# 15_Debug_schdoc.net
KiCad netlist of a schematic drawn in Altium Designer
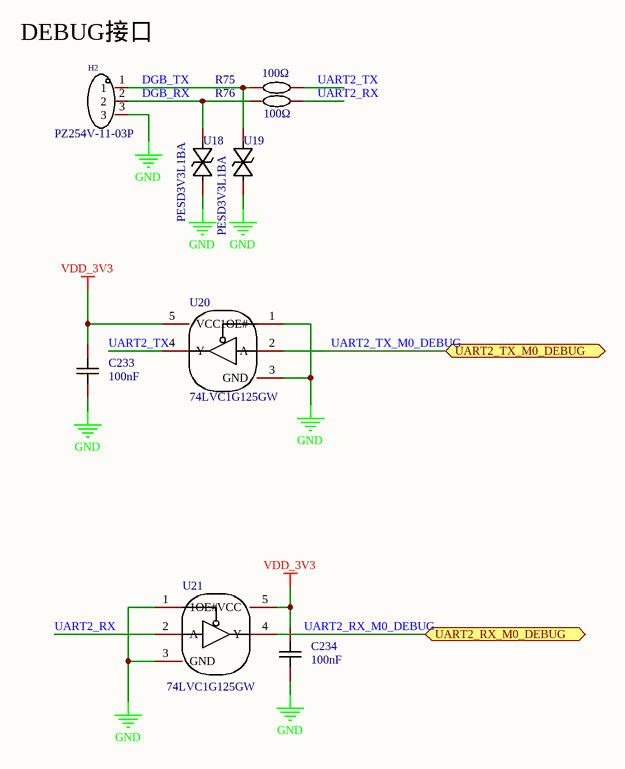
[diagram p0: 15_Debug接口.schdoc.schdoc]

(export (version "E")
  (design (tool "Eeschema 10.0.6"))
  (components
    (comp (ref "C233")
      (value "100nF")
      (footprint "C0603")
      (fields
        (field (name "NAME") "100nF")
        (field (name "MANUFACTURER") "YAGEO(国巨)")
        (field (name "MANUFACTURER PART") "CC0603KRX7R9BB104")
        (field (name "TOLERANCE") "±10%")
      )
      (libsource (lib "altium-import") (part "root_1_CC0603KRX7R9BB104_"))
    )
    (comp (ref "C234")
      (value "100nF")
      (footprint "C0603")
      (fields
        (field (name "NAME") "100nF")
        (field (name "MANUFACTURER") "YAGEO(国巨)")
        (field (name "MANUFACTURER PART") "CC0603KRX7R9BB104")
        (field (name "TOLERANCE") "±10%")
      )
      (libsource (lib "altium-import") (part "root_1_CC0603KRX7R9BB104_"))
    )
    (comp (ref "H2")
      (value "PZ254V-11-03P")
      (footprint "HDR-TH_3P-P2.54-V-M")
      (fields (field (name "NAME") "PZ254V-11-03P") (field (name "MANUFACTURER") "XFCN(兴飞)"))
      (libsource (lib "altium-import") (part "root_0_mirrored_PZ254V-11-03P_"))
    )
    (comp (ref "R75")
      (value "100Ω")
      (footprint "R0603")
      (fields
        (field (name "NAME") "100Ω")
        (field (name "MANUFACTURER") "UNI-ROYAL(厚声)")
        (field (name "MANUFACTURER PART") "0603WAF1000T5E")
        (field (name "TOLERANCE") "±1%")
      )
      (libsource (lib "altium-import") (part "root_0_0603WAF1000T5E_"))
    )
    (comp (ref "R76")
      (value "100Ω")
      (footprint "R0603")
      (fields
        (field (name "NAME") "100Ω")
        (field (name "MANUFACTURER") "UNI-ROYAL(厚声)")
        (field (name "MANUFACTURER PART") "0603WAF1000T5E")
        (field (name "TOLERANCE") "±1%")
      )
      (libsource (lib "altium-import") (part "root_0_0603WAF1000T5E_"))
    )
    (comp (ref "U18")
      (value "PESD3V3L1BA")
      (footprint "SOD-323_L1.7-W1.3-LS2.6-BI")
      (fields (field (name "NAME") "PESD3V3L1BA") (field (name "MANUFACTURER") "UMW(友台半导体)"))
      (libsource (lib "altium-import") (part "root_1_PESD3V3L1BA_C2687129_"))
    )
    (comp (ref "U19")
      (value "PESD3V3L1BA")
      (footprint "SOD-323_L1.7-W1.3-LS2.6-BI")
      (fields (field (name "NAME") "PESD3V3L1BA") (field (name "MANUFACTURER") "UMW(友台半导体)"))
      (libsource (lib "altium-import") (part "root_1_PESD3V3L1BA_C2687129_"))
    )
    (comp (ref "U20")
      (value "74LVC1G125GW,125")
      (footprint "SOT-353_L2.1-W1.3-P0.65-LS2.3-BR")
      (fields (field (name "NAME") "74LVC1G125GW") (field (name "MANUFACTURER") "Nexperia(安世)"))
      (libsource (lib "altium-import") (part "root_0_mirrored_74LVC1G125GW,125_"))
    )
    (comp (ref "U21")
      (value "74LVC1G125GW")
      (footprint "SOT-353_L2.1-W1.3-P0.65-LS2.3-BR")
      (fields
        (field (name "NAME") "74LVC1G125GW")
        (field (name "MANUFACTURER") "Nexperia(安世)")
        (field (name "MANUFACTURER PART") "74LVC1G125GW,125")
      )
      (libsource (lib "altium-import") (part "root_0_74LVC1G125GW,125_"))
    )
  )
  (nets
    (net (code "1") (name "/DGB_RX") (class "Default")
      (node (ref "H2") (pin "2") (pinfunction "2_2") (pintype "passive"))
      (node (ref "R76") (pin "1") (pinfunction "1_1") (pintype "passive"))
      (node (ref "U18") (pin "2") (pinfunction "2_2") (pintype "passive"))
    )
    (net (code "2") (name "/DGB_TX") (class "Default")
      (node (ref "H2") (pin "1") (pinfunction "1_1") (pintype "passive"))
      (node (ref "R75") (pin "1") (pinfunction "1_1") (pintype "passive"))
      (node (ref "U19") (pin "2") (pinfunction "2_2") (pintype "passive"))
    )
    (net (code "3") (name "/UART2_RX") (class "Default")
      (node (ref "R76") (pin "2") (pinfunction "2_2") (pintype "passive"))
      (node (ref "U21") (pin "2") (pinfunction "A_2") (pintype "passive"))
    )
    (net (code "4") (name "/UART2_RX_M0_DEBUG") (class "Default")
      (node (ref "U21") (pin "4") (pinfunction "Y_4") (pintype "passive"))
    )
    (net (code "5") (name "/UART2_TX") (class "Default")
      (node (ref "R75") (pin "2") (pinfunction "2_2") (pintype "passive"))
      (node (ref "U20") (pin "4") (pinfunction "Y_4") (pintype "passive"))
    )
    (net (code "6") (name "/UART2_TX_M0_DEBUG") (class "Default")
      (node (ref "U20") (pin "2") (pinfunction "A_2") (pintype "passive"))
    )
    (net (code "7") (name "GND") (class "Default")
      (node (ref "C233") (pin "1") (pinfunction "1_1") (pintype "passive"))
      (node (ref "C234") (pin "1") (pinfunction "1_1") (pintype "passive"))
      (node (ref "H2") (pin "3") (pinfunction "3_3") (pintype "passive"))
      (node (ref "U18") (pin "1") (pinfunction "1_1") (pintype "passive"))
      (node (ref "U19") (pin "1") (pinfunction "1_1") (pintype "passive"))
      (node (ref "U20") (pin "1") (pinfunction "1OE#_1") (pintype "passive"))
      (node (ref "U20") (pin "3") (pinfunction "GND_3") (pintype "passive"))
      (node (ref "U21") (pin "1") (pinfunction "1OE#_1") (pintype "passive"))
      (node (ref "U21") (pin "3") (pinfunction "GND_3") (pintype "passive"))
    )
    (net (code "8") (name "VDD_3V3") (class "Default")
      (node (ref "C233") (pin "2") (pinfunction "2_2") (pintype "passive"))
      (node (ref "C234") (pin "2") (pinfunction "2_2") (pintype "passive"))
      (node (ref "U20") (pin "5") (pinfunction "VCC_5") (pintype "passive"))
      (node (ref "U21") (pin "5") (pinfunction "VCC_5") (pintype "passive"))
    )
  )
)
